# Dev_Brd_ATSAML10D16A.net
KiCad netlist of a schematic drawn in Altium Designer
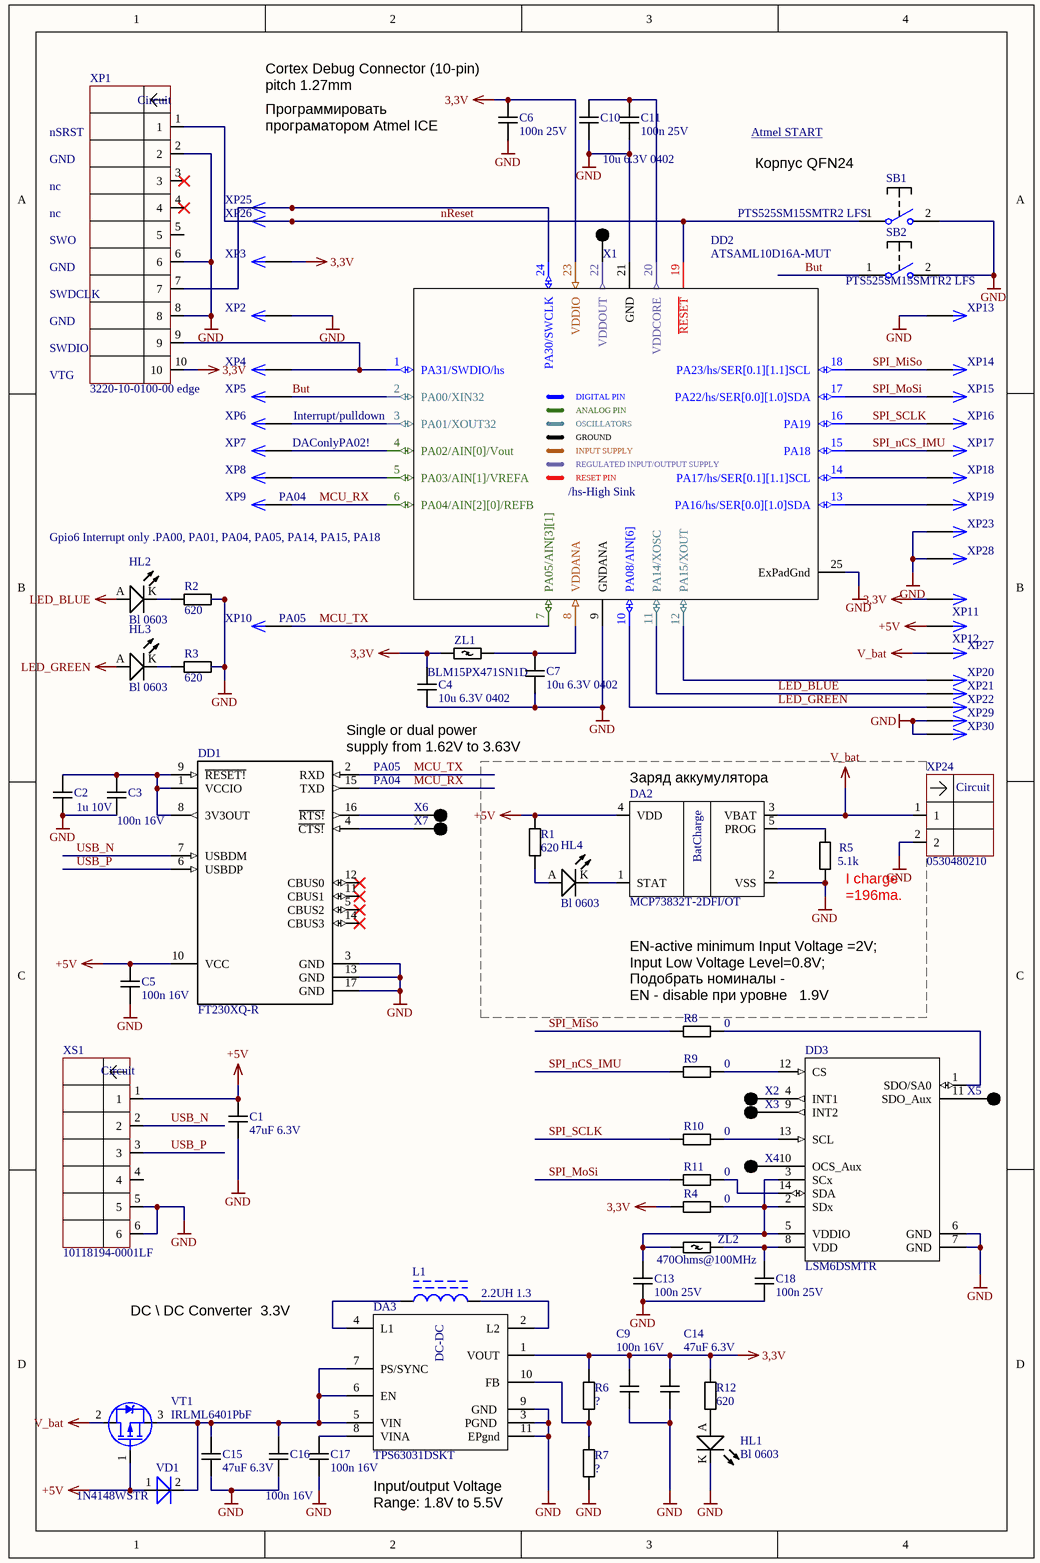
[diagram p0: Dev_Brd_ATSAML10D16A.SchDoc]

(export (version "E")
  (design (tool "Eeschema 10.0.6"))
  (components
    (comp (ref "C1")
      (value "47uF 6.3V")
      (footprint "CapKemet1005(0402)")
      (description "CAP CER 47UF 6.3V X5R 0603")
      (fields
        (field (name "PART NUMBER") "GRM188R60J476ME15D")
        (field (name "DIGI-KEY PART NUMBER") "490-13247-1-ND")
      )
      (libsource (lib "SssAccesDatbase") (part "Cap"))
    )
    (comp (ref "C2")
      (value "1u 10V")
      (footprint "CapKemet1005(0402)")
      (description "CAP CER 1UF 10V 10% X6S 0402")
      (fields
        (field (name "PART NUMBER") "CAPC1005(0402)N")
        (field (name "MANUFACTURER PART NUMBER") "LMK105BJ105KPLF")
      )
      (libsource (lib "") (part "Cap_1"))
    )
    (comp (ref "C3")
      (value "100n 16V")
      (footprint "CapKemet1005(0402)")
      (description "Cap Cer 0.1uF 16V 1% C0G(NP0) MLCC")
      (fields
        (field (name "PART NUMBER") "CL05F104ZO5NNNC")
        (field (name "DIGI-KEY PART NUMBER") "1276-1004-1-ND")
      )
      (libsource (lib "SssAccesDatbase") (part "Cap"))
    )
    (comp (ref "C4")
      (value "10u 6.3V 0402")
      (footprint "CapKemet1005(0402)")
      (description "CAP CER 10UF 6.3V X5R 0402")
      (fields
        (field (name "PART NUMBER") "CAPC1608(0603)")
        (field (name "DIGI-KEY PART NUMBER") "GRJ155R60J106ME11D")
      )
      (libsource (lib "SssAccesDatbase") (part "Cap"))
    )
    (comp (ref "C5")
      (value "100n 16V")
      (footprint "CapKemet1005(0402)")
      (description "Cap Cer 0.1uF 16V 1% C0G(NP0) MLCC")
      (fields
        (field (name "PART NUMBER") "CL05F104ZO5NNNC")
        (field (name "DIGI-KEY PART NUMBER") "1276-1004-1-ND")
      )
      (libsource (lib "SssAccesDatbase") (part "Cap"))
    )
    (comp (ref "C6")
      (value "100n 25V")
      (footprint "CapKemet1005(0402)")
      (description "CAP CER 0.1UF 25V X5R 0402")
      (fields
        (field (name "PART NUMBER") "CAPC1608(0603)")
        (field (name "DIGI-KEY PART NUMBER") "732-7495-1-ND")
      )
      (libsource (lib "") (part "Cap_1"))
    )
    (comp (ref "C7")
      (value "10u 6.3V 0402")
      (footprint "CapKemet1005(0402)")
      (description "CAP CER 10UF 6.3V X5R 0402")
      (fields
        (field (name "PART NUMBER") "CAPC1608(0603)")
        (field (name "DIGI-KEY PART NUMBER") "GRJ155R60J106ME11D")
      )
      (libsource (lib "SssAccesDatbase") (part "Cap"))
    )
    (comp (ref "C9")
      (value "100n 16V")
      (footprint "CapKemet1005(0402)")
      (description "Cap Cer 0.1uF 16V 1% C0G(NP0) MLCC")
      (fields
        (field (name "PART NUMBER") "CL05F104ZO5NNNC")
        (field (name "DIGI-KEY PART NUMBER") "1276-1004-1-ND")
      )
      (libsource (lib "SssAccesDatbase") (part "Cap"))
    )
    (comp (ref "C10")
      (value "10u 6.3V 0402")
      (footprint "CapKemet1005(0402)")
      (description "CAP CER 10UF 6.3V X5R 0402")
      (fields
        (field (name "PART NUMBER") "CAPC1608(0603)")
        (field (name "DIGI-KEY PART NUMBER") "GRJ155R60J106ME11D")
      )
      (libsource (lib "SssAccesDatbase") (part "Cap"))
    )
    (comp (ref "C11")
      (value "100n 25V")
      (footprint "CapKemet1005(0402)")
      (description "CAP CER 0.1UF 25V X5R 0402")
      (fields
        (field (name "PART NUMBER") "CAPC1608(0603)")
        (field (name "DIGI-KEY PART NUMBER") "732-7495-1-ND")
      )
      (libsource (lib "") (part "Cap_1"))
    )
    (comp (ref "C13")
      (value "100n 25V")
      (footprint "CapKemet1005(0402)")
      (description "CAP CER 0.1UF 25V X7R 0402")
      (fields
        (field (name "PART NUMBER") "CL05B104KA5NNNC")
        (field (name "DIGI-KEY PART NUMBER") "1276-6720-1-ND")
      )
      (libsource (lib "SssAccesDatbase") (part "Cap"))
    )
    (comp (ref "C14")
      (value "47uF 6.3V")
      (footprint "CapKemet1005(0402)")
      (description "CAP CER 47UF 6.3V X5R 0603")
      (fields
        (field (name "PART NUMBER") "GRM188R60J476ME15D")
        (field (name "DIGI-KEY PART NUMBER") "490-13247-1-ND")
      )
      (libsource (lib "SssAccesDatbase") (part "Cap"))
    )
    (comp (ref "C15")
      (value "47uF 6.3V")
      (footprint "CapKemet1005(0402)")
      (description "CAP CER 47UF 6.3V X5R 0603")
      (fields
        (field (name "PART NUMBER") "GRM188R60J476ME15D")
        (field (name "DIGI-KEY PART NUMBER") "490-13247-1-ND")
      )
      (libsource (lib "SssAccesDatbase") (part "Cap"))
    )
    (comp (ref "C16")
      (value "100n 16V")
      (footprint "CapKemet1005(0402)")
      (description "Cap Cer 0.1uF 16V 1% C0G(NP0) MLCC")
      (fields
        (field (name "PART NUMBER") "CL05F104ZO5NNNC")
        (field (name "DIGI-KEY PART NUMBER") "1276-1004-1-ND")
      )
      (libsource (lib "SssAccesDatbase") (part "Cap"))
    )
    (comp (ref "C17")
      (value "100n 16V")
      (footprint "CapKemet1005(0402)")
      (description "Cap Cer 0.1uF 16V 1% C0G(NP0) MLCC")
      (fields
        (field (name "PART NUMBER") "CL05F104ZO5NNNC")
        (field (name "DIGI-KEY PART NUMBER") "1276-1004-1-ND")
      )
      (libsource (lib "SssAccesDatbase") (part "Cap"))
    )
    (comp (ref "C18")
      (value "100n 25V")
      (footprint "CapKemet1005(0402)")
      (description "CAP CER 0.1UF 25V X7R 0402")
      (fields
        (field (name "PART NUMBER") "CL05B104KA5NNNC")
        (field (name "DIGI-KEY PART NUMBER") "1276-6720-1-ND")
      )
      (libsource (lib "SssAccesDatbase") (part "Cap"))
    )
    (comp (ref "DA2")
      (value "MCP73832T-2DFI/OT")
      (footprint "SOT-23-5")
      (description "IC LI-ION/LI-POLY CTRLR SOT23-5")
      (fields (field (name "DIGI-KEY PART NUMBER") "MCP73832T-2DFI/OTCT-ND"))
      (libsource (lib "SssAccesDatbase") (part "MCP73832T-2DFI/OT"))
    )
    (comp (ref "DA3")
      (value "TPS63031DSKT")
      (footprint "WSON-10")
      (description "IC REG BCK BST 3.3V 900MA 10SON")
      (fields (field (name "DIGI-KEY PART NUMBER") "296-23904-1-ND"))
      (libsource (lib "SssAccesDatbase") (part "TPS63031DSKR"))
    )
    (comp (ref "DD1")
      (value "FT230XQ-R")
      (footprint "QFN-16(4x4)")
      (description "IC USB SERIAL BASIC UART 16QFN")
      (fields (field (name "DIGI-KEY PART NUMBER") "768-1130-1-ND"))
      (libsource (lib "SssAccesDatbase") (part "FT230XQ-R"))
    )
    (comp (ref "DD2")
      (value "ATSAML10D16A-MUT")
      (footprint "VQFN-24")
      (description "IC MCU 32BIT 64KB FLASH 24VQFN,ARM® Cortex®-M23")
      (fields (field (name "DIGI-KEY PART NUMBER") "ATSAML10D16A-MUTCT-ND"))
      (libsource (lib "SssAccesDatbase") (part "ATSAML10D16A-MUT"))
    )
    (comp (ref "DD3")
      (value "LSM6DSMTR")
      (footprint "LGA-14L_2P5X3X0P83_STM-M")
      (description "IMU ACCEL/GYRO I2C/SPI 14LGA")
      (fields
        (field (name "DIGI-KEY PART NUMBER") "497-16696-1-ND")
        (field (name "MOUSER PART NUMBER") "511-LSM6DSMTR")
        (field (name "COPYRIGHT") "Copyright (C) 2018 Accelerated Designs. All rights reserved")
      )
      (libsource (lib "SssAccesDatbase") (part "LSM6DSMTR"))
    )
    (comp (ref "HL1")
      (value "Bl 0603")
      (footprint "LED-0603-BLUE")
      (description "LED BLUE DIFFUSED 0603 SMD")
      (fields
        (field (name "PART NUMBER") "150060BS55040")
        (field (name "DIGI-KEY PART NUMBER") "732-12013-1-ND")
      )
      (libsource (lib "SssAccesDatbase") (part "LED_AK"))
    )
    (comp (ref "HL2")
      (value "Bl 0603")
      (footprint "LED-0603-BLUE")
      (description "LED BLUE DIFFUSED 0603 SMD")
      (fields
        (field (name "PART NUMBER") "150060BS55040")
        (field (name "DIGI-KEY PART NUMBER") "732-12013-1-ND")
      )
      (libsource (lib "SssAccesDatbase") (part "LED_AK"))
    )
    (comp (ref "HL3")
      (value "Bl 0603")
      (footprint "LED-0603-BLUE")
      (description "LED BLUE DIFFUSED 0603 SMD")
      (fields
        (field (name "PART NUMBER") "150060BS55040")
        (field (name "DIGI-KEY PART NUMBER") "732-12013-1-ND")
      )
      (libsource (lib "SssAccesDatbase") (part "LED_AK"))
    )
    (comp (ref "HL4")
      (value "Bl 0603")
      (footprint "LED-0603-BLUE")
      (description "LED BLUE DIFFUSED 0603 SMD")
      (fields
        (field (name "PART NUMBER") "150060BS55040")
        (field (name "DIGI-KEY PART NUMBER") "732-12013-1-ND")
      )
      (libsource (lib "SssAccesDatbase") (part "LED_AK"))
    )
    (comp (ref "L1")
      (value "2.2UH 1.3")
      (footprint "CDRH2D11")
      (description "FIXED IND 2.2UH 1.3A 120 MOHM")
      (fields
        (field (name "PART NUMBER") "CDRH2D11/HPNP-2R2NC")
        (field (name "DIGI-KEY PART NUMBER") "308-1578-1-ND")
        (field (name "PUBLISHER") "Altium Limited")
      )
      (libsource (lib "SssAccesDatbase") (part "Inductor ferrite"))
    )
    (comp (ref "R1")
      (value "620")
      (footprint "REZKemet 0402")
      (fields (field (name "PART NUMBER") "RESC1005(0402)"))
      (libsource (lib "") (part "Resistor general_1"))
    )
    (comp (ref "R2")
      (value "620")
      (footprint "REZKemet 0402")
      (fields (field (name "PART NUMBER") "RESC1005(0402)"))
      (libsource (lib "SssAccesDatbase") (part "Resistor general"))
    )
    (comp (ref "R3")
      (value "620")
      (footprint "REZKemet 0402")
      (fields (field (name "PART NUMBER") "RESC1005(0402)"))
      (libsource (lib "SssAccesDatbase") (part "Resistor general"))
    )
    (comp (ref "R4")
      (value "0")
      (footprint "REZKemet 0402")
      (description "RES SMD 0402 0 Ohm")
      (fields
        (field (name "PART NUMBER") "RMCF0402ZT0R00")
        (field (name "MOUSER PART NUMBER") "RMCF0402ZT0R00CT-ND")
      )
      (libsource (lib "SssAccesDatbase") (part "Resistor general"))
    )
    (comp (ref "R5")
      (value "5.1k")
      (footprint "REZKemet 0402")
      (description "RES SMD 5.1K OHM 1% 1/10W 0402")
      (fields
        (field (name "PART NUMBER") "RESC1005(0402)")
        (field (name "MANUFACTURER PART NUMBER") "ERJ-2RKF5101X")
      )
      (libsource (lib "") (part "Resistor general_2"))
    )
    (comp (ref "R6")
      (value "?")
      (footprint "REZKemet 0402")
      (fields (field (name "PART NUMBER") "RESC1005(0402)"))
      (libsource (lib "") (part "Resistor general_1"))
    )
    (comp (ref "R7")
      (value "?")
      (footprint "REZKemet 0402")
      (fields (field (name "PART NUMBER") "RESC1005(0402)"))
      (libsource (lib "") (part "Resistor general_1"))
    )
    (comp (ref "R8")
      (value "0")
      (footprint "REZKemet 0402")
      (description "RES SMD 0402 0 Ohm")
      (fields
        (field (name "PART NUMBER") "RMCF0402ZT0R00")
        (field (name "MOUSER PART NUMBER") "RMCF0402ZT0R00CT-ND")
      )
      (libsource (lib "SssAccesDatbase") (part "Resistor general"))
    )
    (comp (ref "R9")
      (value "0")
      (footprint "REZKemet 0402")
      (description "RES SMD 0402 0 Ohm")
      (fields
        (field (name "PART NUMBER") "RMCF0402ZT0R00")
        (field (name "MOUSER PART NUMBER") "RMCF0402ZT0R00CT-ND")
      )
      (libsource (lib "SssAccesDatbase") (part "Resistor general"))
    )
    (comp (ref "R10")
      (value "0")
      (footprint "REZKemet 0402")
      (description "RES SMD 0402 0 Ohm")
      (fields
        (field (name "PART NUMBER") "RMCF0402ZT0R00")
        (field (name "MOUSER PART NUMBER") "RMCF0402ZT0R00CT-ND")
      )
      (libsource (lib "SssAccesDatbase") (part "Resistor general"))
    )
    (comp (ref "R11")
      (value "0")
      (footprint "REZKemet 0402")
      (description "RES SMD 0402 0 Ohm")
      (fields
        (field (name "PART NUMBER") "RMCF0402ZT0R00")
        (field (name "MOUSER PART NUMBER") "RMCF0402ZT0R00CT-ND")
      )
      (libsource (lib "SssAccesDatbase") (part "Resistor general"))
    )
    (comp (ref "R12")
      (value "620")
      (footprint "REZKemet 0402")
      (fields (field (name "PART NUMBER") "RESC1005(0402)"))
      (libsource (lib "") (part "Resistor general_1"))
    )
    (comp (ref "SB1")
      (value "PTS525SM15SMTR2 LFS")
      (footprint "TACT_SWITCH KPT1187B")
      (description "SWITCH TACTILE SPST-NO 0.02A 15V")
      (fields (field (name "DIGI-KEY PART NUMBER") "CKN9104CT-ND"))
      (libsource (lib "SssAccesDatbase") (part "TACT_SWITCH KPT1187B"))
    )
    (comp (ref "SB2")
      (value "PTS525SM15SMTR2 LFS")
      (footprint "TACT_SWITCH KPT1187B")
      (description "SWITCH TACTILE SPST-NO 0.02A 15V")
      (fields (field (name "DIGI-KEY PART NUMBER") "CKN9104CT-ND"))
      (libsource (lib "SssAccesDatbase") (part "TACT_SWITCH KPT1187B"))
    )
    (comp (ref "VD1")
      (value "1N4148WSTR")
      (footprint "SOD323")
      (description "DIODE GEN PURP 75V 300MA SOD323")
      (fields
        (field (name "DIGI-KEY PART NUMBER") "1655-1359-1-ND")
        (field (name "MANUFACTURER PART NUMBER") "?")
        (field (name "PUBLISHER") "Altium Limited")
      )
      (libsource (lib "SssAccesDatbase") (part "Diode"))
    )
    (comp (ref "VT1")
      (value "IRLML6401PbF")
      (footprint "SOT23-3N")
      (fields (field (name "DIGI-KEY PART NUMBER") "???"))
      (libsource (lib "SssAccesDatbase") (part "TRANS-P-Channel-GDS"))
    )
    (comp (ref "X1")
      (value "PLLS1.27-1-TOP-R")
      (footprint "PLLS1.27-1-TOP-R")
      (libsource (lib "SssAccesDatbase") (part "X1_1"))
    )
    (comp (ref "X2")
      (value "PLLS1.27-1-TOP-R")
      (footprint "PLLS1.27-1-TOP-R")
      (libsource (lib "SssAccesDatbase") (part "X1_1"))
    )
    (comp (ref "X3")
      (value "PLLS1.27-1-TOP-R")
      (footprint "PLLS1.27-1-TOP-R")
      (libsource (lib "SssAccesDatbase") (part "X1_1"))
    )
    (comp (ref "X4")
      (value "PLLS1.27-1-TOP-R")
      (footprint "PLLS1.27-1-TOP-R")
      (libsource (lib "SssAccesDatbase") (part "X1_1"))
    )
    (comp (ref "X5")
      (value "PLLS1.27-1-TOP-R")
      (footprint "PLLS1.27-1-TOP-R")
      (libsource (lib "SssAccesDatbase") (part "X1_1"))
    )
    (comp (ref "X6")
      (value "PLLS1.27-1-TOP-R")
      (footprint "PLLS1.27-1-TOP-R")
      (libsource (lib "SssAccesDatbase") (part "X1_1"))
    )
    (comp (ref "X7")
      (value "PLLS1.27-1-TOP-R")
      (footprint "PLLS1.27-1-TOP-R")
      (libsource (lib "SssAccesDatbase") (part "X1_1"))
    )
    (comp (ref "XP1")
      (value "3220-10-0100-00 edge")
      (footprint "IPS 10(1.27)edge")
      (description "3220-10-0100-00")
      (fields (field (name "DIGI-KEY PART NUMBER") "1175-1627-ND"))
      (libsource (lib "SssAccesDatbase") (part "XP-10"))
    )
    (comp (ref "XP2")
      (value "PLS-1")
      (footprint "PLS-1-3D")
      (description "CONN HEADER VERT 1POS")
      (fields
        (field (name "DIGI-KEY PART NUMBER") "S1011EC-01-ND")
        (field (name "MANUFACTURER PART NUMBER") "PRPC001SAAN-RC")
      )
      (libsource (lib "SssAccesDatbase") (part "XP-1_1"))
    )
    (comp (ref "XP3")
      (value "PLS-1")
      (footprint "PLS-1-3D")
      (description "CONN HEADER VERT 1POS")
      (fields
        (field (name "DIGI-KEY PART NUMBER") "S1011EC-01-ND")
        (field (name "MANUFACTURER PART NUMBER") "PRPC001SAAN-RC")
      )
      (libsource (lib "SssAccesDatbase") (part "XP-1_1"))
    )
    (comp (ref "XP4")
      (value "PLS-1")
      (footprint "PLS-1-3D")
      (description "CONN HEADER VERT 1POS")
      (fields
        (field (name "DIGI-KEY PART NUMBER") "S1011EC-01-ND")
        (field (name "MANUFACTURER PART NUMBER") "PRPC001SAAN-RC")
      )
      (libsource (lib "SssAccesDatbase") (part "XP-1_1"))
    )
    (comp (ref "XP5")
      (value "PLS-1")
      (footprint "PLS-1-3D")
      (description "CONN HEADER VERT 1POS")
      (fields
        (field (name "DIGI-KEY PART NUMBER") "S1011EC-01-ND")
        (field (name "MANUFACTURER PART NUMBER") "PRPC001SAAN-RC")
      )
      (libsource (lib "SssAccesDatbase") (part "XP-1_1"))
    )
    (comp (ref "XP6")
      (value "PLS-1")
      (footprint "PLS-1-3D")
      (description "CONN HEADER VERT 1POS")
      (fields
        (field (name "DIGI-KEY PART NUMBER") "S1011EC-01-ND")
        (field (name "MANUFACTURER PART NUMBER") "PRPC001SAAN-RC")
      )
      (libsource (lib "SssAccesDatbase") (part "XP-1_1"))
    )
    (comp (ref "XP7")
      (value "PLS-1")
      (footprint "PLS-1-3D")
      (description "CONN HEADER VERT 1POS")
      (fields
        (field (name "DIGI-KEY PART NUMBER") "S1011EC-01-ND")
        (field (name "MANUFACTURER PART NUMBER") "PRPC001SAAN-RC")
      )
      (libsource (lib "SssAccesDatbase") (part "XP-1_1"))
    )
    (comp (ref "XP8")
      (value "PLS-1")
      (footprint "PLS-1-3D")
      (description "CONN HEADER VERT 1POS")
      (fields
        (field (name "DIGI-KEY PART NUMBER") "S1011EC-01-ND")
        (field (name "MANUFACTURER PART NUMBER") "PRPC001SAAN-RC")
      )
      (libsource (lib "SssAccesDatbase") (part "XP-1_1"))
    )
    (comp (ref "XP9")
      (value "PLS-1")
      (footprint "PLS-1-3D")
      (description "CONN HEADER VERT 1POS")
      (fields
        (field (name "DIGI-KEY PART NUMBER") "S1011EC-01-ND")
        (field (name "MANUFACTURER PART NUMBER") "PRPC001SAAN-RC")
      )
      (libsource (lib "SssAccesDatbase") (part "XP-1_1"))
    )
    (comp (ref "XP10")
      (value "PLS-1")
      (footprint "PLS-1-3D")
      (description "CONN HEADER VERT 1POS")
      (fields
        (field (name "DIGI-KEY PART NUMBER") "S1011EC-01-ND")
        (field (name "MANUFACTURER PART NUMBER") "PRPC001SAAN-RC")
      )
      (libsource (lib "SssAccesDatbase") (part "XP-1_1"))
    )
    (comp (ref "XP11")
      (value "PLS-1")
      (footprint "PLS-1-3D")
      (description "CONN HEADER VERT 1POS")
      (fields
        (field (name "DIGI-KEY PART NUMBER") "S1011EC-01-ND")
        (field (name "MANUFACTURER PART NUMBER") "PRPC001SAAN-RC")
      )
      (libsource (lib "SssAccesDatbase") (part "XP-1_1"))
    )
    (comp (ref "XP12")
      (value "PLS-1")
      (footprint "PLS-1-3D")
      (description "CONN HEADER VERT 1POS")
      (fields
        (field (name "DIGI-KEY PART NUMBER") "S1011EC-01-ND")
        (field (name "MANUFACTURER PART NUMBER") "PRPC001SAAN-RC")
      )
      (libsource (lib "SssAccesDatbase") (part "XP-1_1"))
    )
    (comp (ref "XP13")
      (value "PLS-1")
      (footprint "PLS-1-3D")
      (description "CONN HEADER VERT 1POS")
      (fields
        (field (name "DIGI-KEY PART NUMBER") "S1011EC-01-ND")
        (field (name "MANUFACTURER PART NUMBER") "PRPC001SAAN-RC")
      )
      (libsource (lib "SssAccesDatbase") (part "XP-1_1"))
    )
    (comp (ref "XP14")
      (value "PLS-1")
      (footprint "PLS-1-3D")
      (description "CONN HEADER VERT 1POS")
      (fields
        (field (name "DIGI-KEY PART NUMBER") "S1011EC-01-ND")
        (field (name "MANUFACTURER PART NUMBER") "PRPC001SAAN-RC")
      )
      (libsource (lib "SssAccesDatbase") (part "XP-1_1"))
    )
    (comp (ref "XP15")
      (value "PLS-1")
      (footprint "PLS-1-3D")
      (description "CONN HEADER VERT 1POS")
      (fields
        (field (name "DIGI-KEY PART NUMBER") "S1011EC-01-ND")
        (field (name "MANUFACTURER PART NUMBER") "PRPC001SAAN-RC")
      )
      (libsource (lib "SssAccesDatbase") (part "XP-1_1"))
    )
    (comp (ref "XP16")
      (value "PLS-1")
      (footprint "PLS-1-3D")
      (description "CONN HEADER VERT 1POS")
      (fields
        (field (name "DIGI-KEY PART NUMBER") "S1011EC-01-ND")
        (field (name "MANUFACTURER PART NUMBER") "PRPC001SAAN-RC")
      )
      (libsource (lib "SssAccesDatbase") (part "XP-1_1"))
    )
    (comp (ref "XP17")
      (value "PLS-1")
      (footprint "PLS-1-3D")
      (description "CONN HEADER VERT 1POS")
      (fields
        (field (name "DIGI-KEY PART NUMBER") "S1011EC-01-ND")
        (field (name "MANUFACTURER PART NUMBER") "PRPC001SAAN-RC")
      )
      (libsource (lib "SssAccesDatbase") (part "XP-1_1"))
    )
    (comp (ref "XP18")
      (value "PLS-1")
      (footprint "PLS-1-3D")
      (description "CONN HEADER VERT 1POS")
      (fields
        (field (name "DIGI-KEY PART NUMBER") "S1011EC-01-ND")
        (field (name "MANUFACTURER PART NUMBER") "PRPC001SAAN-RC")
      )
      (libsource (lib "SssAccesDatbase") (part "XP-1_1"))
    )
    (comp (ref "XP19")
      (value "PLS-1")
      (footprint "PLS-1-3D")
      (description "CONN HEADER VERT 1POS")
      (fields
        (field (name "DIGI-KEY PART NUMBER") "S1011EC-01-ND")
        (field (name "MANUFACTURER PART NUMBER") "PRPC001SAAN-RC")
      )
      (libsource (lib "SssAccesDatbase") (part "XP-1_1"))
    )
    (comp (ref "XP20")
      (value "PLS-1")
      (footprint "PLS-1-3D")
      (description "CONN HEADER VERT 1POS")
      (fields
        (field (name "DIGI-KEY PART NUMBER") "S1011EC-01-ND")
        (field (name "MANUFACTURER PART NUMBER") "PRPC001SAAN-RC")
      )
      (libsource (lib "SssAccesDatbase") (part "XP-1_1"))
    )
    (comp (ref "XP21")
      (value "PLS-1")
      (footprint "PLS-1-3D")
      (description "CONN HEADER VERT 1POS")
      (fields
        (field (name "DIGI-KEY PART NUMBER") "S1011EC-01-ND")
        (field (name "MANUFACTURER PART NUMBER") "PRPC001SAAN-RC")
      )
      (libsource (lib "SssAccesDatbase") (part "XP-1_1"))
    )
    (comp (ref "XP22")
      (value "PLS-1")
      (footprint "PLS-1-3D")
      (description "CONN HEADER VERT 1POS")
      (fields
        (field (name "DIGI-KEY PART NUMBER") "S1011EC-01-ND")
        (field (name "MANUFACTURER PART NUMBER") "PRPC001SAAN-RC")
      )
      (libsource (lib "SssAccesDatbase") (part "XP-1_1"))
    )
    (comp (ref "XP23")
      (value "PLS-1")
      (footprint "PLS-1-3D")
      (description "CONN HEADER VERT 1POS")
      (fields
        (field (name "DIGI-KEY PART NUMBER") "S1011EC-01-ND")
        (field (name "MANUFACTURER PART NUMBER") "PRPC001SAAN-RC")
      )
      (libsource (lib "SssAccesDatbase") (part "XP-1_1"))
    )
    (comp (ref "XP24")
      (value "0530480210")
      (footprint "0530480210")
      (description "CONN HEADER R/A 2POS 1.25MM")
      (fields (field (name "DIGI-KEY PART NUMBER") "WM1742-ND"))
      (libsource (lib "SssAccesDatbase") (part "XP-2"))
    )
    (comp (ref "XP25")
      (value "PLS-1")
      (footprint "PLS-1-3D")
      (description "CONN HEADER VERT 1POS")
      (fields
        (field (name "DIGI-KEY PART NUMBER") "S1011EC-01-ND")
        (field (name "MANUFACTURER PART NUMBER") "PRPC001SAAN-RC")
      )
      (libsource (lib "SssAccesDatbase") (part "XP-1_1"))
    )
    (comp (ref "XP26")
      (value "PLS-1")
      (footprint "PLS-1-3D")
      (description "CONN HEADER VERT 1POS")
      (fields
        (field (name "DIGI-KEY PART NUMBER") "S1011EC-01-ND")
        (field (name "MANUFACTURER PART NUMBER") "PRPC001SAAN-RC")
      )
      (libsource (lib "SssAccesDatbase") (part "XP-1_1"))
    )
    (comp (ref "XP27")
      (value "PLS-1")
      (footprint "PLS-1-3D")
      (description "CONN HEADER VERT 1POS")
      (fields
        (field (name "DIGI-KEY PART NUMBER") "S1011EC-01-ND")
        (field (name "MANUFACTURER PART NUMBER") "PRPC001SAAN-RC")
      )
      (libsource (lib "SssAccesDatbase") (part "XP-1_1"))
    )
    (comp (ref "XP28")
      (value "PLS-1")
      (footprint "PLS-1-3D")
      (description "CONN HEADER VERT 1POS")
      (fields
        (field (name "DIGI-KEY PART NUMBER") "S1011EC-01-ND")
        (field (name "MANUFACTURER PART NUMBER") "PRPC001SAAN-RC")
      )
      (libsource (lib "SssAccesDatbase") (part "XP-1_1"))
    )
    (comp (ref "XP29")
      (value "PLS-1")
      (footprint "PLS-1-3D")
      (description "CONN HEADER VERT 1POS")
      (fields
        (field (name "DIGI-KEY PART NUMBER") "S1011EC-01-ND")
        (field (name "MANUFACTURER PART NUMBER") "PRPC001SAAN-RC")
      )
      (libsource (lib "SssAccesDatbase") (part "XP-1_1"))
    )
    (comp (ref "XP30")
      (value "PLS-1")
      (footprint "PLS-1-3D")
      (description "CONN HEADER VERT 1POS")
      (fields
        (field (name "DIGI-KEY PART NUMBER") "S1011EC-01-ND")
        (field (name "MANUFACTURER PART NUMBER") "PRPC001SAAN-RC")
      )
      (libsource (lib "SssAccesDatbase") (part "XP-1_1"))
    )
    (comp (ref "XS1")
      (value "10118194-0001LF")
      (footprint "MICRO_USB _B")
      (description "USB Connectors 5P MICRO USB TYPE B RCPT W/ REAR PEGS")
      (fields
        (field (name "DIGI-KEY PART NUMBER") "609-4618-1-ND")
        (field (name "MOUSER PART NUMBER") "649-10118194-0001LF")
      )
      (libsource (lib "SssAccesDatbase") (part "Micro USB"))
    )
    (comp (ref "ZL1")
      (value "BLM15PX471SN1D")
      (footprint "Ferrite1005(0402)")
      (description "FERRITE BEAD 470 OHM 0402 1LN")
      (fields
        (field (name "PART NUMBER") "Ferrite1005(0402)")
        (field (name "DIGI-KEY PART NUMBER") "490-10662-1-ND")
      )
      (libsource (lib "SssAccesDatbase") (part "ZL"))
    )
    (comp (ref "ZL2")
      (value "470Ohms@100MHz")
      (footprint "Ferrite1005(0402)")
      (description "FERRITE BEAD 470 OHM 0402 1LN")
      (fields
        (field (name "PART NUMBER") "Ferrite1005(0402)")
        (field (name "MANUFACTURER PART NUMBER") "BLM15PX471SN1D")
      )
      (libsource (lib "SssAccesDatbase") (part "ZL"))
    )
  )
  (nets
    (net (code "1") (name "+5V") (class "Default")
      (node (ref "C1") (pin "2") (pinfunction "2_2") (pintype "passive"))
      (node (ref "C5") (pin "2") (pinfunction "2_2") (pintype "passive"))
      (node (ref "DA2") (pin "4") (pinfunction "VDD_4") (pintype "passive"))
      (node (ref "DD1") (pin "10") (pinfunction "VCC_10") (pintype "power_in"))
      (node (ref "R1") (pin "2") (pinfunction "2_2") (pintype "passive"))
      (node (ref "VD1") (pin "1") (pintype "passive"))
      (node (ref "VT1") (pin "1") (pinfunction "G_1") (pintype "passive"))
      (node (ref "XP12") (pin "1") (pinfunction "1_1") (pintype "passive"))
      (node (ref "XS1") (pin "1") (pinfunction "1_1") (pintype "passive"))
    )
    (net (code "2") (name "/But") (class "Default")
      (node (ref "DD2") (pin "2") (pinfunction "PA00/XIN32_2") (pintype "bidirectional"))
      (node (ref "SB2") (pin "1") (pinfunction "COMMON_1") (pintype "passive"))
      (node (ref "XP5") (pin "1") (pinfunction "1_1") (pintype "passive"))
    )
    (net (code "3") (name "/MCU_RX") (class "Default")
      (node (ref "DD1") (pin "15") (pinfunction "TXD_15") (pintype "output"))
      (node (ref "DD2") (pin "6") (pinfunction "PA04/AIN[2][0]/REFB_6") (pintype "bidirectional"))
      (node (ref "XP9") (pin "1") (pinfunction "1_1") (pintype "passive"))
    )
    (net (code "4") (name "/MCU_TX") (class "Default")
      (node (ref "DD1") (pin "2") (pinfunction "RXD_2") (pintype "input"))
      (node (ref "DD2") (pin "7") (pinfunction "PA05/AIN[3][1]_7") (pintype "bidirectional"))
      (node (ref "XP10") (pin "1") (pinfunction "1_1") (pintype "passive"))
    )
    (net (code "5") (name "/SPI_MiSo") (class "Default")
      (node (ref "DD2") (pin "18") (pinfunction "PA23/hs/SER[0.1][1.1]SCL_18") (pintype "bidirectional"))
      (node (ref "R8") (pin "1") (pinfunction "1_1") (pintype "passive"))
      (node (ref "XP14") (pin "1") (pinfunction "1_1") (pintype "passive"))
    )
    (net (code "6") (name "/SPI_MoSi") (class "Default")
      (node (ref "DD2") (pin "17") (pinfunction "PA22/hs/SER[0.0][1.0]SDA_17") (pintype "bidirectional"))
      (node (ref "R11") (pin "1") (pinfunction "1_1") (pintype "passive"))
      (node (ref "XP15") (pin "1") (pinfunction "1_1") (pintype "passive"))
    )
    (net (code "7") (name "/SPI_SCLK") (class "Default")
      (node (ref "DD2") (pin "16") (pinfunction "PA19_16") (pintype "bidirectional"))
      (node (ref "R10") (pin "1") (pinfunction "1_1") (pintype "passive"))
      (node (ref "XP16") (pin "1") (pinfunction "1_1") (pintype "passive"))
    )
    (net (code "8") (name "/SPI_nCS_IMU") (class "Default")
      (node (ref "DD2") (pin "15") (pinfunction "PA18_15") (pintype "bidirectional"))
      (node (ref "R9") (pin "1") (pinfunction "1_1") (pintype "passive"))
      (node (ref "XP17") (pin "1") (pinfunction "1_1") (pintype "passive"))
    )
    (net (code "9") (name "/USB_N") (class "Default")
      (node (ref "DD1") (pin "7") (pinfunction "USBDM_7") (pintype "input"))
      (node (ref "XS1") (pin "2") (pinfunction "2_2") (pintype "passive"))
    )
    (net (code "10") (name "/USB_P") (class "Default")
      (node (ref "DD1") (pin "6") (pinfunction "USBDP_6") (pintype "input"))
      (node (ref "XS1") (pin "3") (pinfunction "3_3") (pintype "passive"))
    )
    (net (code "11") (name "/nReset") (class "Default")
      (node (ref "DD2") (pin "19") (pinfunction "~{RESET}_19") (pintype "passive"))
      (node (ref "SB1") (pin "1") (pinfunction "COMMON_1") (pintype "passive"))
      (node (ref "XP1") (pin "1") (pinfunction "1_1") (pintype "passive"))
      (node (ref "XP26") (pin "1") (pinfunction "1_1") (pintype "passive"))
    )
    (net (code "12") (name "3,3V") (class "Default")
      (node (ref "C14") (pin "2") (pinfunction "2_2") (pintype "passive"))
      (node (ref "C4") (pin "2") (pinfunction "2_2") (pintype "passive"))
      (node (ref "C6") (pin "1") (pinfunction "1_1") (pintype "passive"))
      (node (ref "C9") (pin "2") (pinfunction "2_2") (pintype "passive"))
      (node (ref "DA3") (pin "1") (pinfunction "VOUT_1") (pintype "passive"))
      (node (ref "DD2") (pin "23") (pinfunction "VDDIO_23") (pintype "input"))
      (node (ref "R12") (pin "2") (pinfunction "2_2") (pintype "passive"))
      (node (ref "R4") (pin "1") (pinfunction "1_1") (pintype "passive"))
      (node (ref "R6") (pin "2") (pinfunction "2_2") (pintype "passive"))
      (node (ref "XP1") (pin "10") (pinfunction "10_10") (pintype "passive"))
      (node (ref "XP11") (pin "1") (pinfunction "1_1") (pintype "passive"))
      (node (ref "XP3") (pin "1") (pinfunction "1_1") (pintype "passive"))
      (node (ref "ZL1") (pin "1") (pinfunction "1_1") (pintype "passive"))
    )
    (net (code "13") (name "GND") (class "Default")
      (node (ref "C1") (pin "1") (pinfunction "1_1") (pintype "passive"))
      (node (ref "C10") (pin "1") (pinfunction "1_1") (pintype "passive"))
      (node (ref "C11") (pin "2") (pinfunction "2_2") (pintype "passive"))
      (node (ref "C13") (pin "2") (pinfunction "2_2") (pintype "passive"))
      (node (ref "C14") (pin "1") (pinfunction "1_1") (pintype "passive"))
      (node (ref "C15") (pin "1") (pinfunction "1_1") (pintype "passive"))
      (node (ref "C16") (pin "1") (pinfunction "1_1") (pintype "passive"))
      (node (ref "C17") (pin "1") (pinfunction "1_1") (pintype "passive"))
      (node (ref "C18") (pin "2") (pinfunction "2_2") (pintype "passive"))
      (node (ref "C2") (pin "1") (pinfunction "1_1") (pintype "passive"))
      (node (ref "C3") (pin "1") (pinfunction "1_1") (pintype "passive"))
      (node (ref "C4") (pin "1") (pinfunction "1_1") (pintype "passive"))
      (node (ref "C5") (pin "1") (pinfunction "1_1") (pintype "passive"))
      (node (ref "C6") (pin "2") (pinfunction "2_2") (pintype "passive"))
      (node (ref "C7") (pin "1") (pinfunction "1_1") (pintype "passive"))
      (node (ref "C9") (pin "1") (pinfunction "1_1") (pintype "passive"))
      (node (ref "DA2") (pin "2") (pinfunction "VSS_2") (pintype "passive"))
      (node (ref "DA3") (pin "11") (pinfunction "EPgnd_11") (pintype "passive"))
      (node (ref "DA3") (pin "3") (pinfunction "PGND_3") (pintype "passive"))
      (node (ref "DA3") (pin "9") (pinfunction "GND_9") (pintype "passive"))
      (node (ref "DD1") (pin "13") (pinfunction "GND_13") (pintype "power_in"))
      (node (ref "DD1") (pin "17") (pinfunction "GND_17") (pintype "power_in"))
      (node (ref "DD1") (pin "3") (pinfunction "GND_3") (pintype "power_in"))
      (node (ref "DD2") (pin "21") (pinfunction "GND_21") (pintype "passive"))
      (node (ref "DD2") (pin "25") (pinfunction "ExPadGnd_25") (pintype "passive"))
      (node (ref "DD2") (pin "9") (pinfunction "GNDANA_9") (pintype "passive"))
      (node (ref "DD3") (pin "6") (pinfunction "GND_6") (pintype "passive"))
      (node (ref "DD3") (pin "7") (pinfunction "GND_7") (pintype "passive"))
      (node (ref "HL1") (pin "K") (pinfunction "K_K") (pintype "passive"))
      (node (ref "R2") (pin "2") (pinfunction "2_2") (pintype "passive"))
      (node (ref "R3") (pin "2") (pinfunction "2_2") (pintype "passive"))
      (node (ref "R5") (pin "2") (pinfunction "2_2") (pintype "passive"))
      (node (ref "R7") (pin "1") (pinfunction "1_1") (pintype "passive"))
      (node (ref "SB1") (pin "2") (pinfunction "NO_2") (pintype "passive"))
      (node (ref "SB2") (pin "2") (pinfunction "NO_2") (pintype "passive"))
      (node (ref "XP1") (pin "2") (pinfunction "2_2") (pintype "passive"))
      (node (ref "XP1") (pin "6") (pinfunction "6_6") (pintype "passive"))
      (node (ref "XP1") (pin "8") (pinfunction "8_8") (pintype "passive"))
      (node (ref "XP13") (pin "1") (pinfunction "1_1") (pintype "passive"))
      (node (ref "XP2") (pin "1") (pinfunction "1_1") (pintype "passive"))
      (node (ref "XP23") (pin "1") (pinfunction "1_1") (pintype "passive"))
      (node (ref "XP24") (pin "2") (pinfunction "2_2") (pintype "passive"))
      (node (ref "XP28") (pin "1") (pinfunction "1_1") (pintype "passive"))
      (node (ref "XP29") (pin "1") (pinfunction "1_1") (pintype "passive"))
      (node (ref "XP30") (pin "1") (pinfunction "1_1") (pintype "passive"))
      (node (ref "XS1") (pin "5") (pinfunction "5_5") (pintype "passive"))
      (node (ref "XS1") (pin "6") (pinfunction "6_6") (pintype "passive"))
    )
    (net (code "14") (name "LED_BLUE") (class "Default")
      (node (ref "DD2") (pin "11") (pinfunction "PA14/XOSC_11") (pintype "bidirectional"))
      (node (ref "HL2") (pin "A") (pinfunction "A_A") (pintype "passive"))
      (node (ref "XP21") (pin "1") (pinfunction "1_1") (pintype "passive"))
    )
    (net (code "15") (name "LED_GREEN") (class "Default")
      (node (ref "DD2") (pin "10") (pinfunction "PA08/AIN[6]_10") (pintype "bidirectional"))
      (node (ref "HL3") (pin "A") (pinfunction "A_A") (pintype "passive"))
      (node (ref "XP22") (pin "1") (pinfunction "1_1") (pintype "passive"))
    )
    (net (code "16") (name "Net-(DA2-PROG)") (class "Default")
      (node (ref "DA2") (pin "5") (pinfunction "PROG_5") (pintype "passive"))
      (node (ref "R5") (pin "1") (pinfunction "1_1") (pintype "passive"))
    )
    (net (code "17") (name "Net-(DA2-STAT)") (class "Default")
      (node (ref "DA2") (pin "1") (pinfunction "STAT_1") (pintype "passive"))
      (node (ref "HL4") (pin "K") (pinfunction "K_K") (pintype "passive"))
    )
    (net (code "18") (name "Net-(DA3-EN)") (class "Default")
      (node (ref "C15") (pin "2") (pinfunction "2_2") (pintype "passive"))
      (node (ref "C16") (pin "2") (pinfunction "2_2") (pintype "passive"))
      (node (ref "DA3") (pin "5") (pinfunction "VIN_5") (pintype "passive"))
      (node (ref "DA3") (pin "6") (pinfunction "EN_6") (pintype "passive"))
      (node (ref "DA3") (pin "7") (pinfunction "PS/SYNC_7") (pintype "passive"))
      (node (ref "VD1") (pin "2") (pintype "passive"))
      (node (ref "VT1") (pin "3") (pinfunction "S_3") (pintype "passive"))
    )
    (net (code "19") (name "Net-(DA3-FB)") (class "Default")
      (node (ref "DA3") (pin "10") (pinfunction "FB_10") (pintype "passive"))
      (node (ref "R6") (pin "1") (pinfunction "1_1") (pintype "passive"))
      (node (ref "R7") (pin "2") (pinfunction "2_2") (pintype "passive"))
    )
    (net (code "20") (name "Net-(DA3-L1)") (class "Default")
      (node (ref "DA3") (pin "4") (pinfunction "L1_4") (pintype "passive"))
      (node (ref "L1") (pin "1") (pinfunction "1_1") (pintype "passive"))
    )
    (net (code "21") (name "Net-(DA3-L2)") (class "Default")
      (node (ref "DA3") (pin "2") (pinfunction "L2_2") (pintype "passive"))
      (node (ref "L1") (pin "2") (pinfunction "2_2") (pintype "passive"))
    )
    (net (code "22") (name "Net-(DA3-VINA)") (class "Default")
      (node (ref "C17") (pin "2") (pinfunction "2_2") (pintype "passive"))
      (node (ref "DA3") (pin "8") (pinfunction "VINA_8") (pintype "passive"))
    )
    (net (code "23") (name "Net-(DD1-3V3OUT)") (class "Default")
      (node (ref "C2") (pin "2") (pinfunction "2_2") (pintype "passive"))
      (node (ref "C3") (pin "2") (pinfunction "2_2") (pintype "passive"))
      (node (ref "DD1") (pin "1") (pinfunction "VCCIO_1") (pintype "power_in"))
      (node (ref "DD1") (pin "8") (pinfunction "3V3OUT_8") (pintype "output"))
      (node (ref "DD1") (pin "9") (pinfunction "~{RESET!}_9") (pintype "input"))
    )
    (net (code "24") (name "Net-(DD1-~{CTS!})") (class "Default")
      (node (ref "DD1") (pin "4") (pinfunction "~{CTS!}_4") (pintype "input"))
      (node (ref "X7") (pin "1") (pinfunction "1_1") (pintype "passive"))
    )
    (net (code "25") (name "Net-(DD1-~{RTS!})") (class "Default")
      (node (ref "DD1") (pin "16") (pinfunction "~{RTS!}_16") (pintype "output"))
      (node (ref "X6") (pin "1") (pinfunction "1_1") (pintype "passive"))
    )
    (net (code "26") (name "Net-(DD2-PA01{slash}XOUT32)") (class "Default")
      (node (ref "DD2") (pin "3") (pinfunction "PA01/XOUT32_3") (pintype "bidirectional"))
      (node (ref "XP6") (pin "1") (pinfunction "1_1") (pintype "passive"))
    )
    (net (code "27") (name "Net-(DD2-PA02{slash}AIN[0]{slash}Vout)") (class "Default")
      (node (ref "DD2") (pin "4") (pinfunction "PA02/AIN[0]/Vout_4") (pintype "bidirectional"))
      (node (ref "XP7") (pin "1") (pinfunction "1_1") (pintype "passive"))
    )
    (net (code "28") (name "Net-(DD2-PA03{slash}AIN[1]{slash}VREFA)") (class "Default")
      (node (ref "DD2") (pin "5") (pinfunction "PA03/AIN[1]/VREFA_5") (pintype "bidirectional"))
      (node (ref "XP8") (pin "1") (pinfunction "1_1") (pintype "passive"))
    )
    (net (code "29") (name "Net-(DD2-PA15{slash}XOUT)") (class "Default")
      (node (ref "DD2") (pin "12") (pinfunction "PA15/XOUT_12") (pintype "bidirectional"))
      (node (ref "XP20") (pin "1") (pinfunction "1_1") (pintype "passive"))
    )
    (net (code "30") (name "Net-(DD2-PA16{slash}hs{slash}SER[0.0][1.0]SDA)") (class "Default")
      (node (ref "DD2") (pin "13") (pinfunction "PA16/hs/SER[0.0][1.0]SDA_13") (pintype "bidirectional"))
      (node (ref "XP19") (pin "1") (pinfunction "1_1") (pintype "passive"))
    )
    (net (code "31") (name "Net-(DD2-PA17{slash}hs{slash}SER[0.1][1.1]SCL)") (class "Default")
      (node (ref "DD2") (pin "14") (pinfunction "PA17/hs/SER[0.1][1.1]SCL_14") (pintype "bidirectional"))
      (node (ref "XP18") (pin "1") (pinfunction "1_1") (pintype "passive"))
    )
    (net (code "32") (name "Net-(DD2-PA30{slash}SWCLK)") (class "Default")
      (node (ref "DD2") (pin "24") (pinfunction "PA30/SWCLK_24") (pintype "bidirectional"))
      (node (ref "XP1") (pin "7") (pinfunction "7_7") (pintype "passive"))
      (node (ref "XP25") (pin "1") (pinfunction "1_1") (pintype "passive"))
    )
    (net (code "33") (name "Net-(DD2-PA31{slash}SWDIO{slash}hs)") (class "Default")
      (node (ref "DD2") (pin "1") (pinfunction "PA31/SWDIO/hs_1") (pintype "bidirectional"))
      (node (ref "XP1") (pin "9") (pinfunction "9_9") (pintype "passive"))
      (node (ref "XP4") (pin "1") (pinfunction "1_1") (pintype "passive"))
    )
    (net (code "34") (name "Net-(DD2-VDDANA)") (class "Default")
      (node (ref "C7") (pin "2") (pinfunction "2_2") (pintype "passive"))
      (node (ref "DD2") (pin "8") (pinfunction "VDDANA_8") (pintype "input"))
      (node (ref "ZL1") (pin "2") (pinfunction "2_2") (pintype "passive"))
    )
    (net (code "35") (name "Net-(DD2-VDDCORE)") (class "Default")
      (node (ref "C10") (pin "2") (pinfunction "2_2") (pintype "passive"))
      (node (ref "C11") (pin "1") (pinfunction "1_1") (pintype "passive"))
      (node (ref "DD2") (pin "20") (pinfunction "VDDCORE_20") (pintype "output"))
    )
    (net (code "36") (name "Net-(DD2-VDDOUT)") (class "Default")
      (node (ref "DD2") (pin "22") (pinfunction "VDDOUT_22") (pintype "output"))
      (node (ref "X1") (pin "1") (pinfunction "1_1") (pintype "passive"))
    )
    (net (code "37") (name "Net-(DD3-CS)") (class "Default")
      (node (ref "DD3") (pin "12") (pinfunction "CS_12") (pintype "input"))
      (node (ref "R9") (pin "2") (pinfunction "2_2") (pintype "passive"))
    )
    (net (code "38") (name "Net-(DD3-INT1)") (class "Default")
      (node (ref "DD3") (pin "4") (pinfunction "INT1_4") (pintype "output"))
      (node (ref "X2") (pin "1") (pinfunction "1_1") (pintype "passive"))
    )
    (net (code "39") (name "Net-(DD3-INT2)") (class "Default")
      (node (ref "DD3") (pin "9") (pinfunction "INT2_9") (pintype "output"))
      (node (ref "X3") (pin "1") (pinfunction "1_1") (pintype "passive"))
    )
    (net (code "40") (name "Net-(DD3-OCS_Aux)") (class "Default")
      (node (ref "DD3") (pin "10") (pinfunction "OCS_Aux_10") (pintype "passive"))
      (node (ref "X4") (pin "1") (pinfunction "1_1") (pintype "passive"))
    )
    (net (code "41") (name "Net-(DD3-SCL)") (class "Default")
      (node (ref "DD3") (pin "13") (pinfunction "SCL_13") (pintype "input"))
      (node (ref "R10") (pin "2") (pinfunction "2_2") (pintype "passive"))
    )
    (net (code "42") (name "Net-(DD3-SCx)") (class "Default")
      (node (ref "C13") (pin "1") (pinfunction "1_1") (pintype "passive"))
      (node (ref "DD3") (pin "2") (pinfunction "SDx_2") (pintype "passive"))
      (node (ref "DD3") (pin "3") (pinfunction "SCx_3") (pintype "passive"))
      (node (ref "DD3") (pin "5") (pinfunction "VDDIO_5") (pintype "power_in"))
      (node (ref "R4") (pin "2") (pinfunction "2_2") (pintype "passive"))
      (node (ref "ZL2") (pin "1") (pinfunction "1_1") (pintype "passive"))
    )
    (net (code "43") (name "Net-(DD3-SDA)") (class "Default")
      (node (ref "DD3") (pin "14") (pinfunction "SDA_14") (pintype "bidirectional"))
      (node (ref "R11") (pin "2") (pinfunction "2_2") (pintype "passive"))
    )
    (net (code "44") (name "Net-(DD3-SDO_Aux)") (class "Default")
      (node (ref "DD3") (pin "11") (pinfunction "SDO_Aux_11") (pintype "passive"))
      (node (ref "X5") (pin "1") (pinfunction "1_1") (pintype "passive"))
    )
    (net (code "45") (name "Net-(DD3-SDO{slash}SA0)") (class "Default")
      (node (ref "DD3") (pin "1") (pinfunction "SDO/SA0_1") (pintype "bidirectional"))
      (node (ref "R8") (pin "2") (pinfunction "2_2") (pintype "passive"))
    )
    (net (code "46") (name "Net-(DD3-VDD)") (class "Default")
      (node (ref "C18") (pin "1") (pinfunction "1_1") (pintype "passive"))
      (node (ref "DD3") (pin "8") (pinfunction "VDD_8") (pintype "power_in"))
      (node (ref "ZL2") (pin "2") (pinfunction "2_2") (pintype "passive"))
    )
    (net (code "47") (name "Net-(HL1-PadA)") (class "Default")
      (node (ref "HL1") (pin "A") (pinfunction "A_A") (pintype "passive"))
      (node (ref "R12") (pin "1") (pinfunction "1_1") (pintype "passive"))
    )
    (net (code "48") (name "Net-(HL2-PadK)") (class "Default")
      (node (ref "HL2") (pin "K") (pinfunction "K_K") (pintype "passive"))
      (node (ref "R2") (pin "1") (pinfunction "1_1") (pintype "passive"))
    )
    (net (code "49") (name "Net-(HL3-PadK)") (class "Default")
      (node (ref "HL3") (pin "K") (pinfunction "K_K") (pintype "passive"))
      (node (ref "R3") (pin "1") (pinfunction "1_1") (pintype "passive"))
    )
    (net (code "50") (name "Net-(HL4-PadA)") (class "Default")
      (node (ref "HL4") (pin "A") (pinfunction "A_A") (pintype "passive"))
      (node (ref "R1") (pin "1") (pinfunction "1_1") (pintype "passive"))
    )
    (net (code "51") (name "V_bat") (class "Default")
      (node (ref "DA2") (pin "3") (pinfunction "VBAT_3") (pintype "passive"))
      (node (ref "VT1") (pin "2") (pinfunction "D_2") (pintype "passive"))
      (node (ref "XP24") (pin "1") (pinfunction "1_1") (pintype "passive"))
      (node (ref "XP27") (pin "1") (pinfunction "1_1") (pintype "passive"))
    )
    (net (code "52") (name "unconnected-(DD1-CBUS0-Pad12)") (class "Default")
      (node (ref "DD1") (pin "12") (pinfunction "CBUS0_12") (pintype "bidirectional+no_connect"))
    )
    (net (code "53") (name "unconnected-(DD1-CBUS1-Pad11)") (class "Default")
      (node (ref "DD1") (pin "11") (pinfunction "CBUS1_11") (pintype "bidirectional+no_connect"))
    )
    (net (code "54") (name "unconnected-(DD1-CBUS2-Pad5)") (class "Default")
      (node (ref "DD1") (pin "5") (pinfunction "CBUS2_5") (pintype "bidirectional+no_connect"))
    )
    (net (code "55") (name "unconnected-(DD1-CBUS3-Pad14)") (class "Default")
      (node (ref "DD1") (pin "14") (pinfunction "CBUS3_14") (pintype "bidirectional+no_connect"))
    )
    (net (code "56") (name "unconnected-(XP1-Pad3)") (class "Default")
      (node (ref "XP1") (pin "3") (pinfunction "3_3") (pintype "passive+no_connect"))
    )
    (net (code "57") (name "unconnected-(XP1-Pad4)") (class "Default")
      (node (ref "XP1") (pin "4") (pinfunction "4_4") (pintype "passive+no_connect"))
    )
    (net (code "58") (name "unconnected-(XP1-Pad5)") (class "Default")
      (node (ref "XP1") (pin "5") (pinfunction "5_5") (pintype "passive"))
    )
    (net (code "59") (name "unconnected-(XS1-Pad4)") (class "Default")
      (node (ref "XS1") (pin "4") (pinfunction "4_4") (pintype "passive"))
    )
  )
)
